# CameraBoard.net
KiCad netlist of a schematic drawn in EAGLE
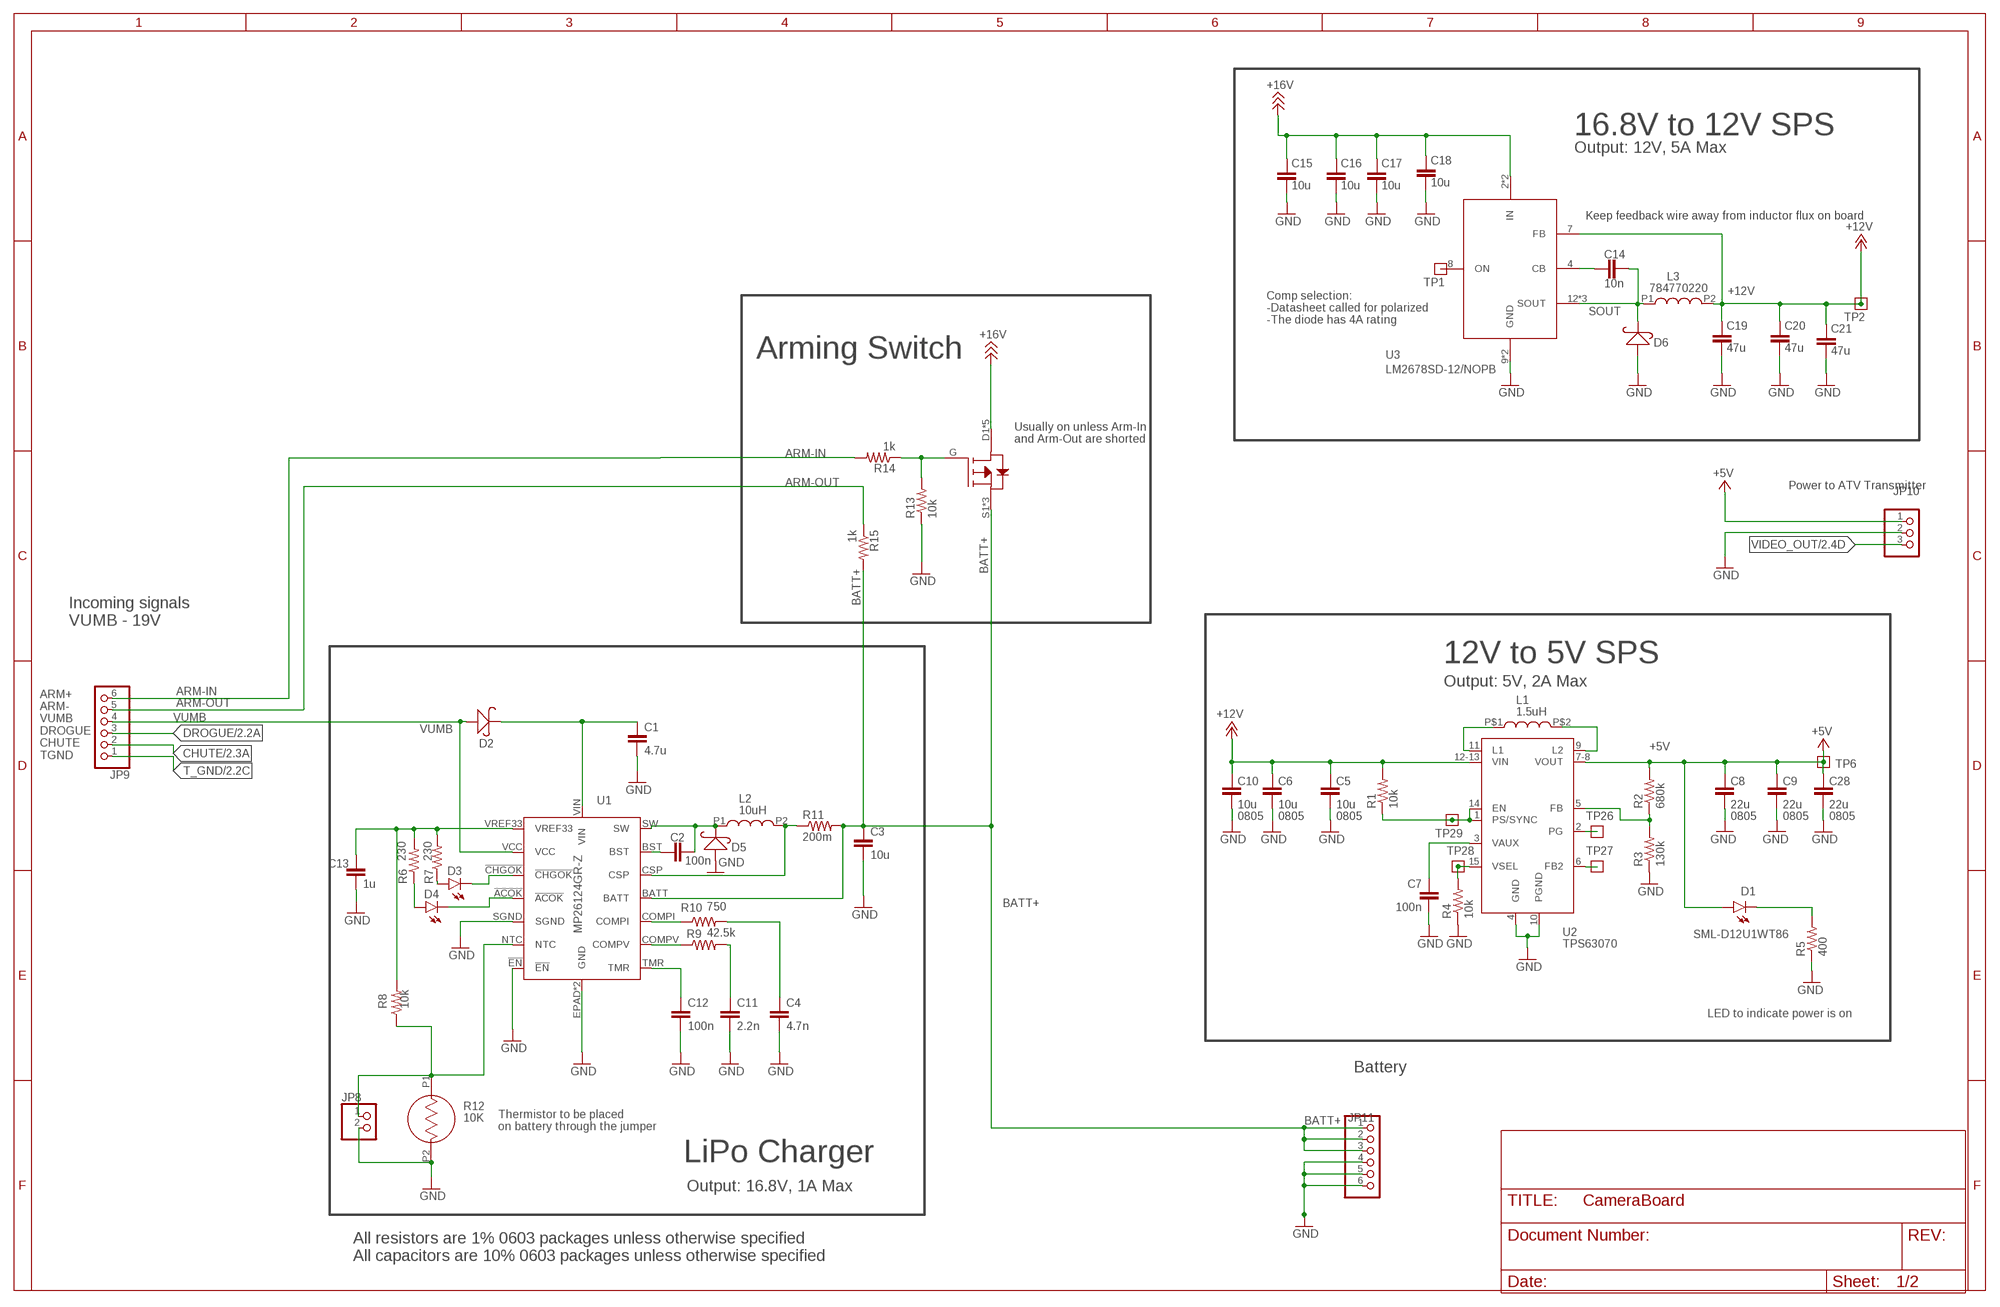
[diagram p0: schematic, sheet 1]
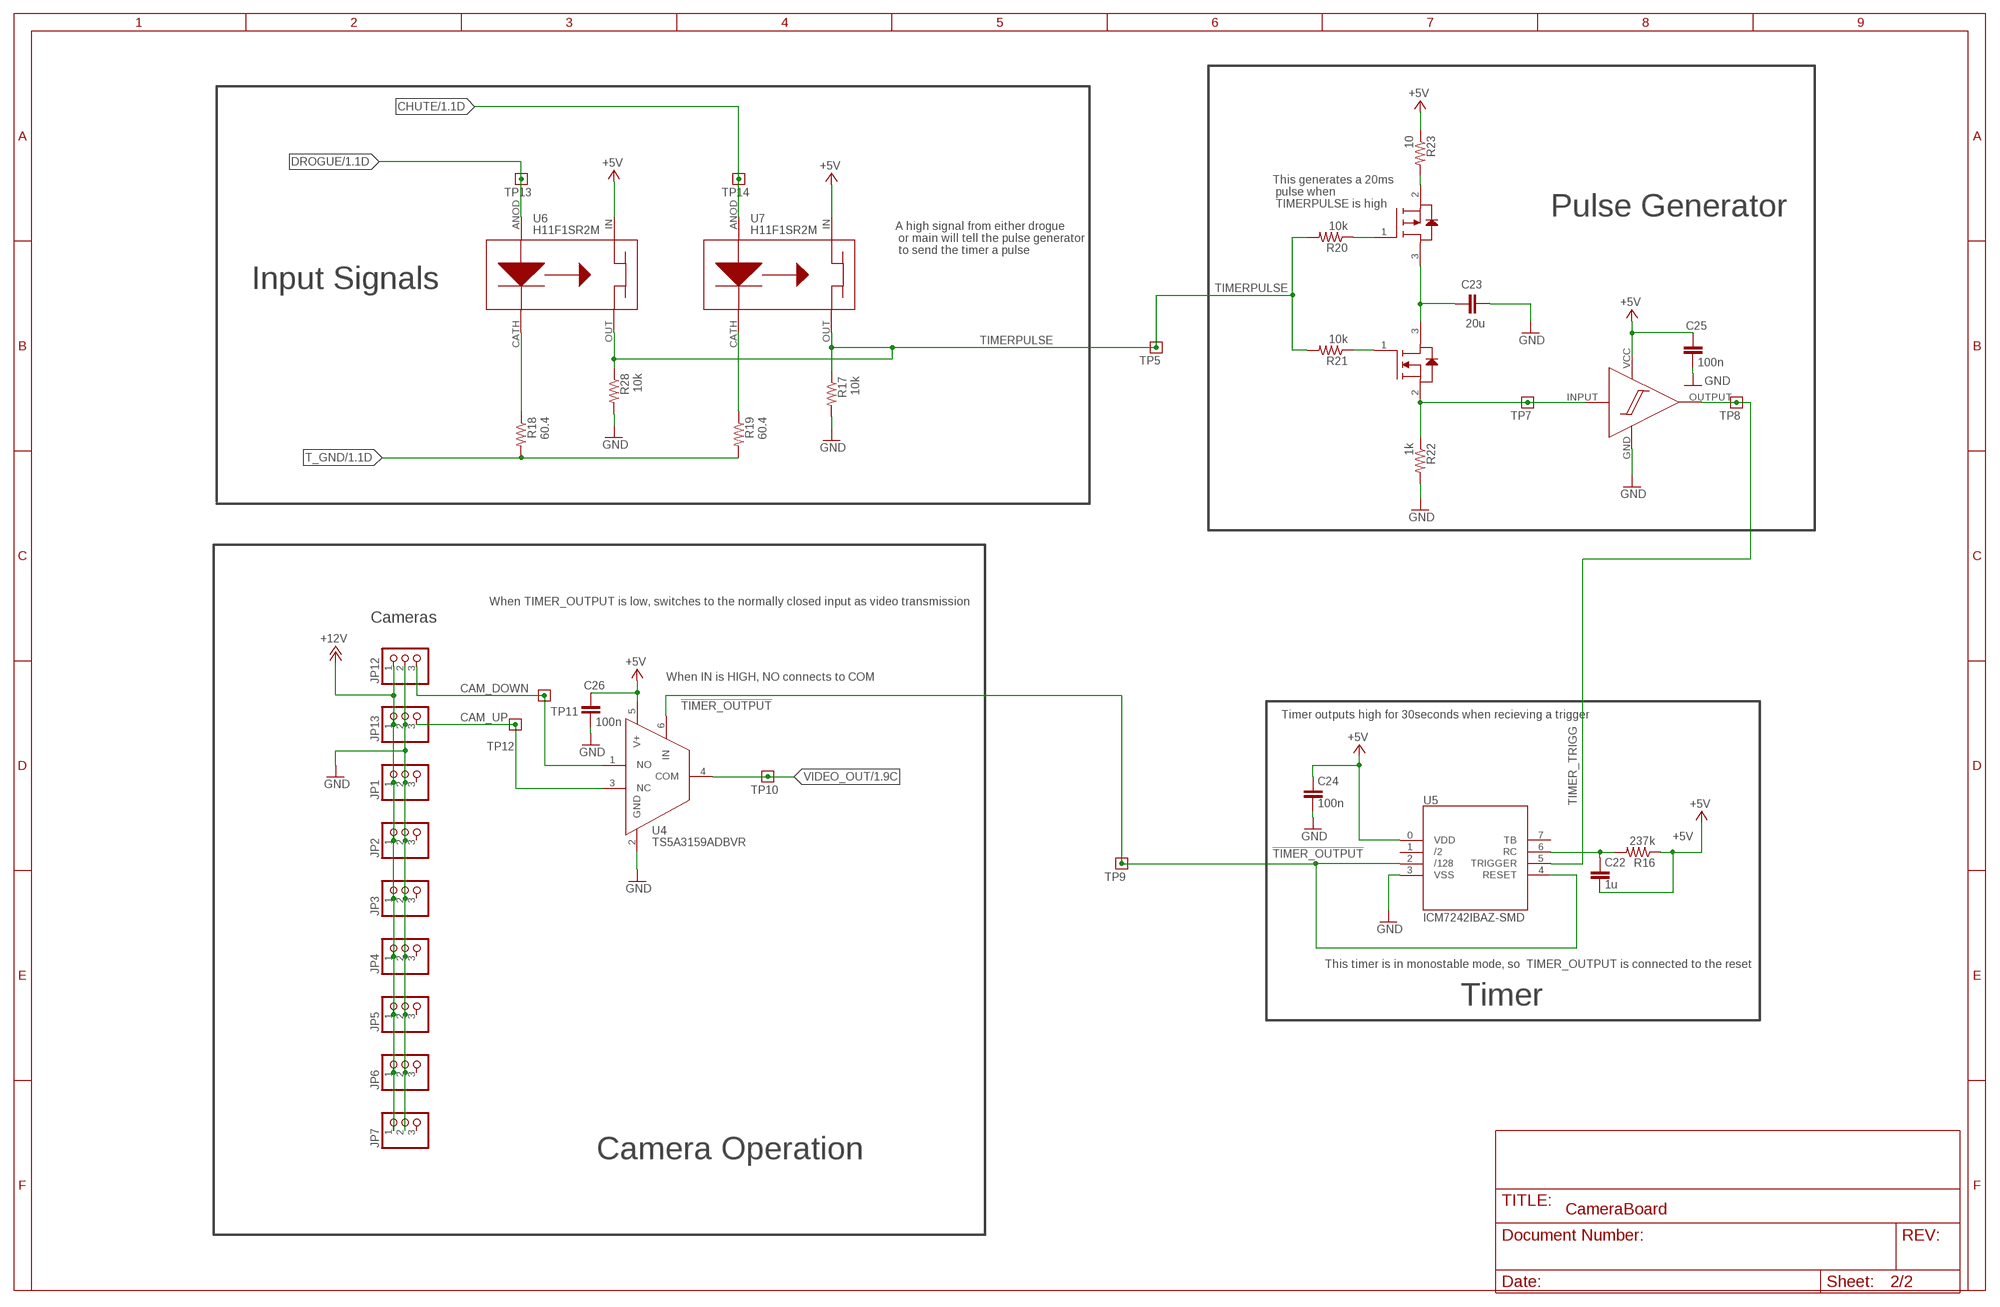
[diagram p1: schematic, sheet 2]

(export (version "E")
  (design (tool "Eeschema 10.0.6"))
  (components
    (comp (ref "C1")
      (value "4.7u")
      (footprint "eagle-import:.0603-A-NOSILK")
      (libsource (lib "eagle-import") (part "C-EU0603-A-NOSILK"))
    )
    (comp (ref "C2")
      (value "100n")
      (footprint "eagle-import:.0603-A-NOSILK")
      (libsource (lib "eagle-import") (part "C-EU0603-A-NOSILK"))
    )
    (comp (ref "C3")
      (value "10u")
      (footprint "eagle-import:.0603-A-NOSILK")
      (libsource (lib "eagle-import") (part "C-EU0603-A-NOSILK"))
    )
    (comp (ref "C4")
      (value "4.7n")
      (footprint "eagle-import:.0603-A-NOSILK")
      (libsource (lib "eagle-import") (part "C-EU0603-A-NOSILK"))
    )
    (comp (ref "C5")
      (value "10u")
      (footprint "eagle-import:.0805-C-NOSILK")
      (fields (field (name "MFR") "Samsung") (field (name "MPN") "CL05B104KO5NNNC"))
      (libsource (lib "eagle-import") (part "C-EU0805-C-NOSILK"))
    )
    (comp (ref "C6")
      (value "10u")
      (footprint "eagle-import:.0805-C-NOSILK")
      (libsource (lib "eagle-import") (part "C-EU0805-C-NOSILK"))
    )
    (comp (ref "C7")
      (value "100n")
      (footprint "eagle-import:.0603-C-NOSILK")
      (fields (field (name "MFR") "Samsung") (field (name "MPN") "CL05B104KO5NNNC"))
      (libsource (lib "eagle-import") (part "C-EU0603-C-NOSILK"))
    )
    (comp (ref "C8")
      (value "22u")
      (footprint "eagle-import:.0805-C-NOSILK")
      (fields (field (name "MFR") "Samsung") (field (name "MPN") "CL05B104KO5NNNC"))
      (libsource (lib "eagle-import") (part "C-EU0805-C-NOSILK"))
    )
    (comp (ref "C9")
      (value "22u")
      (footprint "eagle-import:.0805-C-NOSILK")
      (libsource (lib "eagle-import") (part "C-EU0805-C-NOSILK"))
    )
    (comp (ref "C10")
      (value "10u")
      (footprint "eagle-import:.0805-C-NOSILK")
      (libsource (lib "eagle-import") (part "C-EU0805-C-NOSILK"))
    )
    (comp (ref "C11")
      (value "2.2n")
      (footprint "eagle-import:.0603-A-NOSILK")
      (libsource (lib "eagle-import") (part "C-EU0603-A-NOSILK"))
    )
    (comp (ref "C12")
      (value "100n")
      (footprint "eagle-import:.0603-A-NOSILK")
      (libsource (lib "eagle-import") (part "C-EU0603-A-NOSILK"))
    )
    (comp (ref "C13")
      (value "1u")
      (footprint "eagle-import:.0603-A-NOSILK")
      (libsource (lib "eagle-import") (part "C-EU0603-A-NOSILK"))
    )
    (comp (ref "C14")
      (value "10n")
      (footprint "eagle-import:.0603-A-NOSILK")
      (libsource (lib "eagle-import") (part "C-EU0603-A-NOSILK"))
    )
    (comp (ref "C15")
      (value "10u")
      (footprint "eagle-import:.0805-B-NOSILK")
      (libsource (lib "eagle-import") (part "C-EU0805-B-NOSILK"))
    )
    (comp (ref "C16")
      (value "10u")
      (footprint "eagle-import:.0805-B-NOSILK")
      (libsource (lib "eagle-import") (part "C-EU0805-B-NOSILK"))
    )
    (comp (ref "C17")
      (value "10u")
      (footprint "eagle-import:.0805-B-NOSILK")
      (libsource (lib "eagle-import") (part "C-EU0805-B-NOSILK"))
    )
    (comp (ref "C18")
      (value "10u")
      (footprint "eagle-import:.0805-B-NOSILK")
      (libsource (lib "eagle-import") (part "C-EU0805-B-NOSILK"))
    )
    (comp (ref "C19")
      (value "47u")
      (footprint "eagle-import:1206-A")
      (libsource (lib "eagle-import") (part "C-EU1206-A"))
    )
    (comp (ref "C20")
      (value "47u")
      (footprint "eagle-import:1206-A")
      (libsource (lib "eagle-import") (part "C-EU1206-A"))
    )
    (comp (ref "C21")
      (value "47u")
      (footprint "eagle-import:1206-A")
      (libsource (lib "eagle-import") (part "C-EU1206-A"))
    )
    (comp (ref "C28")
      (value "22u")
      (footprint "eagle-import:.0805-C-NOSILK")
      (libsource (lib "eagle-import") (part "C-EU0805-C-NOSILK"))
    )
    (comp (ref "D1")
      (value "SML-D12U1WT86")
      (footprint "eagle-import:CHIPLED_0603")
      (fields (field (name "MPN") "SML-D12M1WT86"))
      (libsource (lib "eagle-import") (part "LEDCHIPLED_0603"))
    )
    (comp (ref "D2")
      (value "S2MA-13-F")
      (footprint "eagle-import:S2MA-13-F")
      (libsource (lib "eagle-import") (part "S2MA-13-F"))
    )
    (comp (ref "D3")
      (value "SML-D12U1WT86")
      (footprint "eagle-import:CHIPLED_0603")
      (fields (field (name "MPN") "SML-D12M1WT86"))
      (libsource (lib "eagle-import") (part "LEDCHIPLED_0603"))
    )
    (comp (ref "D4")
      (value "SML-D12U1WT86")
      (footprint "eagle-import:CHIPLED_0603")
      (fields (field (name "MPN") "SML-D12M1WT86"))
      (libsource (lib "eagle-import") (part "LEDCHIPLED_0603"))
    )
    (comp (ref "D5")
      (value "S2MA-13-F")
      (footprint "eagle-import:S2MA-13-F")
      (libsource (lib "eagle-import") (part "S2MA-13-F"))
    )
    (comp (ref "D6")
      (value "D_MBRS340T3G")
      (footprint "eagle-import:SMC")
      (fields (field (name "MANUFACTURER_PART_NUMBER") "MBRS340T3G"))
      (libsource (lib "eagle-import") (part "D_MBRS340T3G"))
    )
    (comp (ref "JP8")
      (value "PINHD-1X2")
      (footprint "eagle-import:1X02")
      (libsource (lib "eagle-import") (part "PINHD-1X2"))
    )
    (comp (ref "JP9")
      (value "PINHD-1X6")
      (footprint "eagle-import:1X06")
      (libsource (lib "eagle-import") (part "PINHD-1X6"))
    )
    (comp (ref "JP10")
      (value "PINHD-1X3")
      (footprint "eagle-import:1X03")
      (libsource (lib "eagle-import") (part "PINHD-1X3"))
    )
    (comp (ref "JP11")
      (value "PINHD-1X6")
      (footprint "eagle-import:1X06")
      (libsource (lib "eagle-import") (part "PINHD-1X6"))
    )
    (comp (ref "L1")
      (value "1.5uH")
      (footprint "eagle-import:IHLP2020CZER1R5M11")
      (fields (field (name "MFR") "Vishay Dale") (field (name "MPN") "IHLP2020BZER4R7M11"))
      (libsource (lib "eagle-import") (part "IHLP2020CZER1R5M11"))
    )
    (comp (ref "L2")
      (value "10uH")
      (footprint "eagle-import:1239AS-H-100M=P2")
      (fields (field (name "MPN") "1239AS-H-100M=P2"))
      (libsource (lib "eagle-import") (part "1239AS-H-100M=P2"))
    )
    (comp (ref "L3")
      (value "784770220")
      (footprint "eagle-import:784770220")
      (libsource (lib "eagle-import") (part "784770220"))
    )
    (comp (ref "Q1")
      (value "SI7465DP-T1-E3")
      (footprint "eagle-import:SI7465DP-T1-E3CT-ND")
      (fields (field (name "MFR") "Vishay Siliconix"))
      (libsource (lib "eagle-import") (part "SI7465DP-T1-E3"))
    )
    (comp (ref "R1")
      (value "10k")
      (footprint "eagle-import:.0603-C-NOSILK")
      (fields (field (name "MFR") "Samsung") (field (name "MPN") "RC1005F6653CS"))
      (libsource (lib "eagle-import") (part "R-US_0603-C-NOSILK"))
    )
    (comp (ref "R2")
      (value "680k")
      (footprint "eagle-import:.0603-C-NOSILK")
      (fields (field (name "MFR") "Samsung") (field (name "MPN") "RC1005F6653CS"))
      (libsource (lib "eagle-import") (part "R-US_0603-C-NOSILK"))
    )
    (comp (ref "R3")
      (value "130k")
      (footprint "eagle-import:.0603-C-NOSILK")
      (fields (field (name "MFR") "Samsung") (field (name "MPN") "RC1005F6653CS"))
      (libsource (lib "eagle-import") (part "R-US_0603-C-NOSILK"))
    )
    (comp (ref "R4")
      (value "10k")
      (footprint "eagle-import:.0603-C-NOSILK")
      (fields (field (name "MFR") "Samsung") (field (name "MPN") "RC1005F6653CS"))
      (libsource (lib "eagle-import") (part "R-US_0603-C-NOSILK"))
    )
    (comp (ref "R5")
      (value "400")
      (footprint "eagle-import:.0603-C-NOSILK")
      (fields (field (name "MFR") "Samsung") (field (name "MPN") "RC1005F6653CS"))
      (libsource (lib "eagle-import") (part "R-US_0603-C-NOSILK"))
    )
    (comp (ref "R6")
      (value "230")
      (footprint "eagle-import:.0603-A-NOSILK")
      (libsource (lib "eagle-import") (part "R-US_0603-A-NOSILK"))
    )
    (comp (ref "R7")
      (value "230")
      (footprint "eagle-import:.0603-A-NOSILK")
      (libsource (lib "eagle-import") (part "R-US_0603-A-NOSILK"))
    )
    (comp (ref "R8")
      (value "10k")
      (footprint "eagle-import:.0603-A-NOSILK")
      (libsource (lib "eagle-import") (part "R-US_0603-A-NOSILK"))
    )
    (comp (ref "R9")
      (value "42.5k")
      (footprint "eagle-import:.0603-A-NOSILK")
      (libsource (lib "eagle-import") (part "R-US_0603-A-NOSILK"))
    )
    (comp (ref "R10")
      (value "750")
      (footprint "eagle-import:.0603-A-NOSILK")
      (libsource (lib "eagle-import") (part "R-US_0603-A-NOSILK"))
    )
    (comp (ref "R11")
      (value "200m")
      (footprint "eagle-import:1206-A")
      (libsource (lib "eagle-import") (part "R-US_1206-A"))
    )
    (comp (ref "R12")
      (value "10K")
      (footprint "eagle-import:NHQ103B375T10")
      (fields (field (name "MPN") "NHQ103B375T10"))
      (libsource (lib "eagle-import") (part "NHQ103B375T10"))
    )
    (comp (ref "R13")
      (value "10k")
      (footprint "eagle-import:.0603-A-NOSILK")
      (libsource (lib "eagle-import") (part "R-US_0603-A-NOSILK"))
    )
    (comp (ref "R14")
      (value "1k")
      (footprint "eagle-import:.0603-A-NOSILK")
      (libsource (lib "eagle-import") (part "R-US_0603-A-NOSILK"))
    )
    (comp (ref "R15")
      (value "1k")
      (footprint "eagle-import:.0603-A-NOSILK")
      (libsource (lib "eagle-import") (part "R-US_0603-A-NOSILK"))
    )
    (comp (ref "TP1")
      (value "TEST-POINT")
      (footprint "eagle-import:2MM-TEST-POINT")
      (libsource (lib "eagle-import") (part "TEST-POINT"))
    )
    (comp (ref "TP2")
      (value "TEST-POINT")
      (footprint "eagle-import:2MM-TEST-POINT")
      (libsource (lib "eagle-import") (part "TEST-POINT"))
    )
    (comp (ref "TP6")
      (value "TEST-POINT")
      (footprint "eagle-import:2MM-TEST-POINT")
      (libsource (lib "eagle-import") (part "TEST-POINT"))
    )
    (comp (ref "TP26")
      (value "TEST-POINT")
      (footprint "eagle-import:2MM-TEST-POINT")
      (libsource (lib "eagle-import") (part "TEST-POINT"))
    )
    (comp (ref "TP27")
      (value "TEST-POINT")
      (footprint "eagle-import:2MM-TEST-POINT")
      (libsource (lib "eagle-import") (part "TEST-POINT"))
    )
    (comp (ref "TP28")
      (value "TEST-POINT")
      (footprint "eagle-import:2MM-TEST-POINT")
      (libsource (lib "eagle-import") (part "TEST-POINT"))
    )
    (comp (ref "TP29")
      (value "TEST-POINT")
      (footprint "eagle-import:2MM-TEST-POINT")
      (libsource (lib "eagle-import") (part "TEST-POINT"))
    )
    (comp (ref "U1")
      (value "MP26124GR-Z")
      (footprint "eagle-import:MP26124GR-Z")
      (libsource (lib "eagle-import") (part "MP26124GR-Z"))
    )
    (comp (ref "U2")
      (value "TPS63070")
      (footprint "eagle-import:TPS63070X")
      (fields (field (name "MPN") "TPS63070RNMR"))
      (libsource (lib "eagle-import") (part "TPS63070X"))
    )
    (comp (ref "U3")
      (value "LM2678SD-12/NOPB")
      (footprint "eagle-import:LM2678SD-12_NOPB")
      (libsource (lib "eagle-import") (part "LM2678SD-12/NOPB"))
    )
    (comp (ref "C22")
      (value "1u")
      (footprint "eagle-import:.0603-C-NOSILK")
      (libsource (lib "eagle-import") (part "C-EU0603-C-NOSILK"))
    )
    (comp (ref "C23")
      (value "20u")
      (footprint "eagle-import:.0603-C-NOSILK")
      (libsource (lib "eagle-import") (part "C-EU0603-C-NOSILK"))
    )
    (comp (ref "C24")
      (value "100n")
      (footprint "eagle-import:.0603-C-NOSILK")
      (libsource (lib "eagle-import") (part "C-EU0603-C-NOSILK"))
    )
    (comp (ref "C25")
      (value "100n")
      (footprint "eagle-import:.0603-C-NOSILK")
      (libsource (lib "eagle-import") (part "C-EU0603-C-NOSILK"))
    )
    (comp (ref "C26")
      (value "100n")
      (footprint "eagle-import:.0603-C-NOSILK")
      (libsource (lib "eagle-import") (part "C-EU0603-C-NOSILK"))
    )
    (comp (ref "JP1")
      (value "PINHD-1X3")
      (footprint "eagle-import:1X03")
      (libsource (lib "eagle-import") (part "PINHD-1X3"))
    )
    (comp (ref "JP2")
      (value "PINHD-1X3")
      (footprint "eagle-import:1X03")
      (libsource (lib "eagle-import") (part "PINHD-1X3"))
    )
    (comp (ref "JP3")
      (value "PINHD-1X3")
      (footprint "eagle-import:1X03")
      (libsource (lib "eagle-import") (part "PINHD-1X3"))
    )
    (comp (ref "JP4")
      (value "PINHD-1X3")
      (footprint "eagle-import:1X03")
      (libsource (lib "eagle-import") (part "PINHD-1X3"))
    )
    (comp (ref "JP5")
      (value "PINHD-1X3")
      (footprint "eagle-import:1X03")
      (libsource (lib "eagle-import") (part "PINHD-1X3"))
    )
    (comp (ref "JP6")
      (value "PINHD-1X3")
      (footprint "eagle-import:1X03")
      (libsource (lib "eagle-import") (part "PINHD-1X3"))
    )
    (comp (ref "JP7")
      (value "PINHD-1X3")
      (footprint "eagle-import:1X03")
      (libsource (lib "eagle-import") (part "PINHD-1X3"))
    )
    (comp (ref "JP12")
      (value "PINHD-1X3")
      (footprint "eagle-import:1X03")
      (libsource (lib "eagle-import") (part "PINHD-1X3"))
    )
    (comp (ref "JP13")
      (value "PINHD-1X3")
      (footprint "eagle-import:1X03")
      (libsource (lib "eagle-import") (part "PINHD-1X3"))
    )
    (comp (ref "Q2")
      (value "BVSS123LT1G")
      (footprint "eagle-import:BVSS123LT1G")
      (libsource (lib "eagle-import") (part "BVSS123LT1G"))
    )
    (comp (ref "Q3")
      (value "BSS84")
      (footprint "eagle-import:BSS84")
      (libsource (lib "eagle-import") (part "BSS84"))
    )
    (comp (ref "R16")
      (value "237k")
      (footprint "eagle-import:.0603-A-NOSILK")
      (libsource (lib "eagle-import") (part "R-US_0603-A-NOSILK"))
    )
    (comp (ref "R17")
      (value "10k")
      (footprint "eagle-import:.0603-C-NOSILK")
      (libsource (lib "eagle-import") (part "R-US_0603-C-NOSILK"))
    )
    (comp (ref "R18")
      (value "60.4")
      (footprint "eagle-import:.0603-C-NOSILK")
      (libsource (lib "eagle-import") (part "R-US_0603-C-NOSILK"))
    )
    (comp (ref "R19")
      (value "60.4")
      (footprint "eagle-import:.0603-C-NOSILK")
      (libsource (lib "eagle-import") (part "R-US_0603-C-NOSILK"))
    )
    (comp (ref "R20")
      (value "10k")
      (footprint "eagle-import:.0603-A-NOSILK")
      (libsource (lib "eagle-import") (part "R-US_0603-A-NOSILK"))
    )
    (comp (ref "R21")
      (value "10k")
      (footprint "eagle-import:.0603-A-NOSILK")
      (libsource (lib "eagle-import") (part "R-US_0603-A-NOSILK"))
    )
    (comp (ref "R22")
      (value "1k")
      (footprint "eagle-import:.0603-A-NOSILK")
      (libsource (lib "eagle-import") (part "R-US_0603-A-NOSILK"))
    )
    (comp (ref "R23")
      (value "10")
      (footprint "eagle-import:.0805-A-NOSILK")
      (libsource (lib "eagle-import") (part "R-US_0805-A-NOSILK"))
    )
    (comp (ref "R28")
      (value "10k")
      (footprint "eagle-import:.0603-C-NOSILK")
      (libsource (lib "eagle-import") (part "R-US_0603-C-NOSILK"))
    )
    (comp (ref "TP5")
      (value "TEST-POINT")
      (footprint "eagle-import:2MM-TEST-POINT")
      (libsource (lib "eagle-import") (part "TEST-POINT"))
    )
    (comp (ref "TP7")
      (value "TEST-POINT")
      (footprint "eagle-import:2MM-TEST-POINT")
      (libsource (lib "eagle-import") (part "TEST-POINT"))
    )
    (comp (ref "TP8")
      (value "TEST-POINT")
      (footprint "eagle-import:2MM-TEST-POINT")
      (libsource (lib "eagle-import") (part "TEST-POINT"))
    )
    (comp (ref "TP9")
      (value "TEST-POINT")
      (footprint "eagle-import:2MM-TEST-POINT")
      (libsource (lib "eagle-import") (part "TEST-POINT"))
    )
    (comp (ref "TP10")
      (value "TEST-POINT")
      (footprint "eagle-import:2MM-TEST-POINT")
      (libsource (lib "eagle-import") (part "TEST-POINT"))
    )
    (comp (ref "TP11")
      (value "TEST-POINT")
      (footprint "eagle-import:2MM-TEST-POINT")
      (libsource (lib "eagle-import") (part "TEST-POINT"))
    )
    (comp (ref "TP12")
      (value "TEST-POINT")
      (footprint "eagle-import:2MM-TEST-POINT")
      (libsource (lib "eagle-import") (part "TEST-POINT"))
    )
    (comp (ref "TP13")
      (value "TEST-POINT")
      (footprint "eagle-import:2MM-TEST-POINT")
      (libsource (lib "eagle-import") (part "TEST-POINT"))
    )
    (comp (ref "TP14")
      (value "TEST-POINT")
      (footprint "eagle-import:2MM-TEST-POINT")
      (libsource (lib "eagle-import") (part "TEST-POINT"))
    )
    (comp (ref "U4")
      (value "TS5A3159ADBVR")
      (footprint "eagle-import:TS5A3159ADBVR")
      (libsource (lib "eagle-import") (part "TS5A3159ADBVR"))
    )
    (comp (ref "U5")
      (value "ICM7242IBAZ-SMD")
      (footprint "eagle-import:ICM7242IBAZ-SMD")
      (fields (field (name "MPN") "ICM7242IBAZ"))
      (libsource (lib "eagle-import") (part "ICM7242IBAZ-SMD"))
    )
    (comp (ref "U6")
      (value "H11F1SR2M")
      (footprint "eagle-import:H11F1SR2M")
      (libsource (lib "eagle-import") (part "H11F1SR2M"))
    )
    (comp (ref "U7")
      (value "H11F1SR2M")
      (footprint "eagle-import:H11F1SR2M")
      (libsource (lib "eagle-import") (part "H11F1SR2M"))
    )
    (comp (ref "U8")
      (value "SN74LVC1G17DCKR")
      (footprint "eagle-import:SN74LVC1G17DCKR")
      (libsource (lib "eagle-import") (part "SN74LVC1G17DCKR"))
    )
  )
  (nets
    (net (code "1") (name "+5V") (class "Default")
      (node (ref "C22") (pin "2") (pinfunction "2_2") (pintype "passive"))
      (node (ref "C24") (pin "1") (pinfunction "1_1") (pintype "passive"))
      (node (ref "C25") (pin "2") (pinfunction "2_2") (pintype "passive"))
      (node (ref "C26") (pin "2") (pinfunction "2_2") (pintype "passive"))
      (node (ref "C28") (pin "1") (pinfunction "1_1") (pintype "passive"))
      (node (ref "C8") (pin "1") (pinfunction "1_1") (pintype "passive"))
      (node (ref "C9") (pin "1") (pinfunction "1_1") (pintype "passive"))
      (node (ref "D1") (pin "A") (pinfunction "A_A") (pintype "passive"))
      (node (ref "JP10") (pin "1") (pinfunction "1_1") (pintype "passive"))
      (node (ref "R16") (pin "1") (pinfunction "1_1") (pintype "passive"))
      (node (ref "R2") (pin "2") (pinfunction "2_2") (pintype "passive"))
      (node (ref "R23") (pin "1") (pinfunction "1_1") (pintype "passive"))
      (node (ref "TP6") (pin "1") (pinfunction "1_1") (pintype "passive"))
      (node (ref "U2") (pin "7-8") (pinfunction "VOUT_7-8") (pintype "power_in"))
      (node (ref "U4") (pin "5") (pinfunction "V+_5") (pintype "bidirectional"))
      (node (ref "U5") (pin "0") (pinfunction "VDD_0") (pintype "bidirectional"))
      (node (ref "U6") (pin "IN") (pinfunction "IN_IN") (pintype "bidirectional"))
      (node (ref "U7") (pin "IN") (pinfunction "IN_IN") (pintype "bidirectional"))
      (node (ref "U8") (pin "VCC") (pinfunction "VCC_VCC") (pintype "bidirectional"))
    )
    (net (code "2") (name "+12V") (class "Default")
      (node (ref "C10") (pin "1") (pinfunction "1_1") (pintype "passive"))
      (node (ref "C19") (pin "1") (pinfunction "1_1") (pintype "passive"))
      (node (ref "C20") (pin "1") (pinfunction "1_1") (pintype "passive"))
      (node (ref "C21") (pin "1") (pinfunction "1_1") (pintype "passive"))
      (node (ref "C5") (pin "1") (pinfunction "1_1") (pintype "passive"))
      (node (ref "C6") (pin "1") (pinfunction "1_1") (pintype "passive"))
      (node (ref "JP1") (pin "1") (pinfunction "1_1") (pintype "passive"))
      (node (ref "JP12") (pin "1") (pinfunction "1_1") (pintype "passive"))
      (node (ref "JP13") (pin "1") (pinfunction "1_1") (pintype "passive"))
      (node (ref "JP2") (pin "1") (pinfunction "1_1") (pintype "passive"))
      (node (ref "JP3") (pin "1") (pinfunction "1_1") (pintype "passive"))
      (node (ref "JP4") (pin "1") (pinfunction "1_1") (pintype "passive"))
      (node (ref "JP5") (pin "1") (pinfunction "1_1") (pintype "passive"))
      (node (ref "JP6") (pin "1") (pinfunction "1_1") (pintype "passive"))
      (node (ref "JP7") (pin "1") (pinfunction "1_1") (pintype "passive"))
      (node (ref "L3") (pin "P2") (pinfunction "P$2_P2") (pintype "bidirectional"))
      (node (ref "R1") (pin "2") (pinfunction "2_2") (pintype "passive"))
      (node (ref "TP2") (pin "1") (pinfunction "1_1") (pintype "passive"))
      (node (ref "U2") (pin "12-13") (pinfunction "VIN_12-13") (pintype "power_in"))
      (node (ref "U3") (pin "7") (pinfunction "FB_7") (pintype "bidirectional"))
    )
    (net (code "3") (name "+16V") (class "Default")
      (node (ref "C15") (pin "1") (pinfunction "1_1") (pintype "passive"))
      (node (ref "C16") (pin "1") (pinfunction "1_1") (pintype "passive"))
      (node (ref "C17") (pin "1") (pinfunction "1_1") (pintype "passive"))
      (node (ref "C18") (pin "1") (pinfunction "1_1") (pintype "passive"))
      (node (ref "Q1") (pin "D1") (pinfunction "D_D1") (pintype "bidirectional"))
      (node (ref "Q1") (pin "D2") (pinfunction "D_D2") (pintype "bidirectional"))
      (node (ref "Q1") (pin "D3") (pinfunction "D_D3") (pintype "bidirectional"))
      (node (ref "Q1") (pin "D4") (pinfunction "D_D4") (pintype "bidirectional"))
      (node (ref "Q1") (pin "DPAD") (pinfunction "D_DPAD") (pintype "bidirectional"))
      (node (ref "U3") (pin "2") (pinfunction "IN_2") (pintype "bidirectional"))
      (node (ref "U3") (pin "3") (pinfunction "IN_3") (pintype "bidirectional"))
    )
    (net (code "4") (name "ARM-IN") (class "Default")
      (node (ref "JP9") (pin "6") (pinfunction "6_6") (pintype "passive"))
      (node (ref "R14") (pin "2") (pinfunction "2_2") (pintype "passive"))
    )
    (net (code "5") (name "ARM-OUT") (class "Default")
      (node (ref "JP9") (pin "5") (pinfunction "5_5") (pintype "passive"))
      (node (ref "R15") (pin "1") (pinfunction "1_1") (pintype "passive"))
    )
    (net (code "6") (name "BATT+") (class "Default")
      (node (ref "C3") (pin "1") (pinfunction "1_1") (pintype "passive"))
      (node (ref "JP11") (pin "1") (pinfunction "1_1") (pintype "passive"))
      (node (ref "JP11") (pin "2") (pinfunction "2_2") (pintype "passive"))
      (node (ref "JP11") (pin "3") (pinfunction "3_3") (pintype "passive"))
      (node (ref "Q1") (pin "S1") (pinfunction "S_S1") (pintype "bidirectional"))
      (node (ref "Q1") (pin "S2") (pinfunction "S_S2") (pintype "bidirectional"))
      (node (ref "Q1") (pin "S3") (pinfunction "S_S3") (pintype "bidirectional"))
      (node (ref "R11") (pin "2") (pinfunction "2_2") (pintype "passive"))
      (node (ref "R15") (pin "2") (pinfunction "2_2") (pintype "passive"))
      (node (ref "U1") (pin "BATT") (pinfunction "BATT_BATT") (pintype "bidirectional"))
    )
    (net (code "7") (name "CAM_DOWN") (class "Default")
      (node (ref "JP12") (pin "3") (pinfunction "3_3") (pintype "passive"))
      (node (ref "TP11") (pin "1") (pinfunction "1_1") (pintype "passive"))
      (node (ref "U4") (pin "1") (pinfunction "NO_1") (pintype "bidirectional"))
    )
    (net (code "8") (name "CAM_UP") (class "Default")
      (node (ref "JP13") (pin "3") (pinfunction "3_3") (pintype "passive"))
      (node (ref "TP12") (pin "1") (pinfunction "1_1") (pintype "passive"))
      (node (ref "U4") (pin "3") (pinfunction "NC_3") (pintype "bidirectional"))
    )
    (net (code "9") (name "CHUTE") (class "Default")
      (node (ref "JP9") (pin "2") (pinfunction "2_2") (pintype "passive"))
      (node (ref "TP14") (pin "1") (pinfunction "1_1") (pintype "passive"))
      (node (ref "U7") (pin "ANOD") (pinfunction "ANOD_ANOD") (pintype "bidirectional"))
    )
    (net (code "10") (name "DROGUE") (class "Default")
      (node (ref "JP9") (pin "3") (pinfunction "3_3") (pintype "passive"))
      (node (ref "TP13") (pin "1") (pinfunction "1_1") (pintype "passive"))
      (node (ref "U6") (pin "ANOD") (pinfunction "ANOD_ANOD") (pintype "bidirectional"))
    )
    (net (code "11") (name "GND") (class "Default")
      (node (ref "C1") (pin "2") (pinfunction "2_2") (pintype "passive"))
      (node (ref "C10") (pin "2") (pinfunction "2_2") (pintype "passive"))
      (node (ref "C11") (pin "2") (pinfunction "2_2") (pintype "passive"))
      (node (ref "C12") (pin "2") (pinfunction "2_2") (pintype "passive"))
      (node (ref "C13") (pin "2") (pinfunction "2_2") (pintype "passive"))
      (node (ref "C15") (pin "2") (pinfunction "2_2") (pintype "passive"))
      (node (ref "C16") (pin "2") (pinfunction "2_2") (pintype "passive"))
      (node (ref "C17") (pin "2") (pinfunction "2_2") (pintype "passive"))
      (node (ref "C18") (pin "2") (pinfunction "2_2") (pintype "passive"))
      (node (ref "C19") (pin "2") (pinfunction "2_2") (pintype "passive"))
      (node (ref "C20") (pin "2") (pinfunction "2_2") (pintype "passive"))
      (node (ref "C21") (pin "2") (pinfunction "2_2") (pintype "passive"))
      (node (ref "C23") (pin "2") (pinfunction "2_2") (pintype "passive"))
      (node (ref "C24") (pin "2") (pinfunction "2_2") (pintype "passive"))
      (node (ref "C25") (pin "1") (pinfunction "1_1") (pintype "passive"))
      (node (ref "C26") (pin "1") (pinfunction "1_1") (pintype "passive"))
      (node (ref "C28") (pin "2") (pinfunction "2_2") (pintype "passive"))
      (node (ref "C3") (pin "2") (pinfunction "2_2") (pintype "passive"))
      (node (ref "C4") (pin "2") (pinfunction "2_2") (pintype "passive"))
      (node (ref "C5") (pin "2") (pinfunction "2_2") (pintype "passive"))
      (node (ref "C6") (pin "2") (pinfunction "2_2") (pintype "passive"))
      (node (ref "C7") (pin "2") (pinfunction "2_2") (pintype "passive"))
      (node (ref "C8") (pin "2") (pinfunction "2_2") (pintype "passive"))
      (node (ref "C9") (pin "2") (pinfunction "2_2") (pintype "passive"))
      (node (ref "D5") (pin "ANODE") (pinfunction "+_ANODE") (pintype "passive"))
      (node (ref "D6") (pin "2") (pinfunction "+_2") (pintype "passive"))
      (node (ref "JP1") (pin "2") (pinfunction "2_2") (pintype "passive"))
      (node (ref "JP10") (pin "2") (pinfunction "2_2") (pintype "passive"))
      (node (ref "JP11") (pin "4") (pinfunction "4_4") (pintype "passive"))
      (node (ref "JP11") (pin "5") (pinfunction "5_5") (pintype "passive"))
      (node (ref "JP11") (pin "6") (pinfunction "6_6") (pintype "passive"))
      (node (ref "JP12") (pin "2") (pinfunction "2_2") (pintype "passive"))
      (node (ref "JP13") (pin "2") (pinfunction "2_2") (pintype "passive"))
      (node (ref "JP2") (pin "2") (pinfunction "2_2") (pintype "passive"))
      (node (ref "JP3") (pin "2") (pinfunction "2_2") (pintype "passive"))
      (node (ref "JP4") (pin "2") (pinfunction "2_2") (pintype "passive"))
      (node (ref "JP5") (pin "2") (pinfunction "2_2") (pintype "passive"))
      (node (ref "JP6") (pin "2") (pinfunction "2_2") (pintype "passive"))
      (node (ref "JP7") (pin "2") (pinfunction "2_2") (pintype "passive"))
      (node (ref "JP8") (pin "2") (pinfunction "2_2") (pintype "passive"))
      (node (ref "R12") (pin "P2") (pinfunction "P$2_P2") (pintype "bidirectional"))
      (node (ref "R13") (pin "1") (pinfunction "1_1") (pintype "passive"))
      (node (ref "R17") (pin "2") (pinfunction "2_2") (pintype "passive"))
      (node (ref "R22") (pin "2") (pinfunction "2_2") (pintype "passive"))
      (node (ref "R28") (pin "2") (pinfunction "2_2") (pintype "passive"))
      (node (ref "R3") (pin "1") (pinfunction "1_1") (pintype "passive"))
      (node (ref "R4") (pin "1") (pinfunction "1_1") (pintype "passive"))
      (node (ref "R5") (pin "1") (pinfunction "1_1") (pintype "passive"))
      (node (ref "U1") (pin "!EN") (pinfunction "~{EN}_!EN") (pintype "bidirectional"))
      (node (ref "U1") (pin "EPAD") (pinfunction "GND_EPAD") (pintype "bidirectional"))
      (node (ref "U1") (pin "GND") (pinfunction "GND_GND") (pintype "bidirectional"))
      (node (ref "U1") (pin "SGND") (pinfunction "SGND_SGND") (pintype "bidirectional"))
      (node (ref "U2") (pin "10") (pinfunction "PGND_10") (pintype "power_in"))
      (node (ref "U2") (pin "4") (pinfunction "GND_4") (pintype "power_in"))
      (node (ref "U3") (pin "9") (pinfunction "GND_9") (pintype "bidirectional"))
      (node (ref "U3") (pin "DAP") (pinfunction "GND_DAP") (pintype "bidirectional"))
      (node (ref "U4") (pin "2") (pinfunction "GND_2") (pintype "bidirectional"))
      (node (ref "U5") (pin "3") (pinfunction "VSS_3") (pintype "bidirectional"))
      (node (ref "U8") (pin "GND") (pinfunction "GND_GND") (pintype "bidirectional"))
    )
    (net (code "12") (name "Net-(C2-Pad2)") (class "Default")
      (node (ref "C2") (pin "2") (pinfunction "2_2") (pintype "passive"))
      (node (ref "U1") (pin "BST") (pinfunction "BST_BST") (pintype "bidirectional"))
    )
    (net (code "13") (name "Net-(C4-Pad1)") (class "Default")
      (node (ref "C4") (pin "1") (pinfunction "1_1") (pintype "passive"))
      (node (ref "R10") (pin "2") (pinfunction "2_2") (pintype "passive"))
    )
    (net (code "14") (name "Net-(C11-Pad1)") (class "Default")
      (node (ref "C11") (pin "1") (pinfunction "1_1") (pintype "passive"))
      (node (ref "R9") (pin "2") (pinfunction "2_2") (pintype "passive"))
    )
    (net (code "15") (name "Net-(C12-Pad1)") (class "Default")
      (node (ref "C12") (pin "1") (pinfunction "1_1") (pintype "passive"))
      (node (ref "U1") (pin "TMR") (pinfunction "TMR_TMR") (pintype "bidirectional"))
    )
    (net (code "16") (name "Net-(C13-Pad1)") (class "Default")
      (node (ref "C13") (pin "1") (pinfunction "1_1") (pintype "passive"))
      (node (ref "R6") (pin "2") (pinfunction "2_2") (pintype "passive"))
      (node (ref "R7") (pin "2") (pinfunction "2_2") (pintype "passive"))
      (node (ref "R8") (pin "2") (pinfunction "2_2") (pintype "passive"))
      (node (ref "U1") (pin "VREF33") (pinfunction "VREF33_VREF33") (pintype "bidirectional"))
    )
    (net (code "17") (name "Net-(D1-PadC)") (class "Default")
      (node (ref "D1") (pin "C") (pinfunction "C_C") (pintype "passive"))
      (node (ref "R5") (pin "2") (pinfunction "2_2") (pintype "passive"))
    )
    (net (code "18") (name "Net-(D2--)") (class "Default")
      (node (ref "C1") (pin "1") (pinfunction "1_1") (pintype "passive"))
      (node (ref "D2") (pin "CATHODE") (pinfunction "-_CATHODE") (pintype "passive"))
      (node (ref "U1") (pin "VIN") (pinfunction "VIN_VIN") (pintype "bidirectional"))
    )
    (net (code "19") (name "Net-(D3-PadA)") (class "Default")
      (node (ref "D3") (pin "A") (pinfunction "A_A") (pintype "passive"))
      (node (ref "R7") (pin "1") (pinfunction "1_1") (pintype "passive"))
    )
    (net (code "20") (name "Net-(D4-PadA)") (class "Default")
      (node (ref "D4") (pin "A") (pinfunction "A_A") (pintype "passive"))
      (node (ref "R6") (pin "1") (pinfunction "1_1") (pintype "passive"))
    )
    (net (code "21") (name "Net-(D5--)") (class "Default")
      (node (ref "C2") (pin "1") (pinfunction "1_1") (pintype "passive"))
      (node (ref "D5") (pin "CATHODE") (pinfunction "-_CATHODE") (pintype "passive"))
      (node (ref "L2") (pin "P1") (pinfunction "P$1_P1") (pintype "bidirectional"))
      (node (ref "U1") (pin "SW") (pinfunction "SW_SW") (pintype "bidirectional"))
    )
    (net (code "22") (name "Net-(L2-P$2)") (class "Default")
      (node (ref "L2") (pin "P2") (pinfunction "P$2_P2") (pintype "bidirectional"))
      (node (ref "R11") (pin "1") (pinfunction "1_1") (pintype "passive"))
      (node (ref "U1") (pin "CSP") (pinfunction "CSP_CSP") (pintype "bidirectional"))
    )
    (net (code "23") (name "Net-(Q1-PadG)") (class "Default")
      (node (ref "Q1") (pin "G") (pinfunction "G_G") (pintype "bidirectional"))
      (node (ref "R13") (pin "2") (pinfunction "2_2") (pintype "passive"))
      (node (ref "R14") (pin "1") (pinfunction "1_1") (pintype "passive"))
    )
    (net (code "24") (name "Net-(Q2-D)") (class "Default")
      (node (ref "C23") (pin "1") (pinfunction "1_1") (pintype "passive"))
      (node (ref "Q2") (pin "3") (pinfunction "D_3") (pintype "bidirectional"))
      (node (ref "Q3") (pin "3") (pinfunction "D_3") (pintype "bidirectional"))
    )
    (net (code "25") (name "Net-(Q2-G)") (class "Default")
      (node (ref "Q2") (pin "1") (pinfunction "G_1") (pintype "bidirectional"))
      (node (ref "R21") (pin "1") (pinfunction "1_1") (pintype "passive"))
    )
    (net (code "26") (name "Net-(Q2-S)") (class "Default")
      (node (ref "Q2") (pin "2") (pinfunction "S_2") (pintype "bidirectional"))
      (node (ref "R22") (pin "1") (pinfunction "1_1") (pintype "passive"))
      (node (ref "TP7") (pin "1") (pinfunction "1_1") (pintype "passive"))
      (node (ref "U8") (pin "INPUT") (pinfunction "A_INPUT") (pintype "bidirectional"))
    )
    (net (code "27") (name "Net-(Q3-G)") (class "Default")
      (node (ref "Q3") (pin "1") (pinfunction "G_1") (pintype "bidirectional"))
      (node (ref "R20") (pin "1") (pinfunction "1_1") (pintype "passive"))
    )
    (net (code "28") (name "Net-(Q3-S)") (class "Default")
      (node (ref "Q3") (pin "2") (pinfunction "S_2") (pintype "bidirectional"))
      (node (ref "R23") (pin "2") (pinfunction "2_2") (pintype "passive"))
    )
    (net (code "29") (name "Net-(R9-Pad1)") (class "Default")
      (node (ref "R9") (pin "1") (pinfunction "1_1") (pintype "passive"))
      (node (ref "U1") (pin "COMPV") (pinfunction "COMPV_COMPV") (pintype "bidirectional"))
    )
    (net (code "30") (name "Net-(R10-Pad1)") (class "Default")
      (node (ref "R10") (pin "1") (pinfunction "1_1") (pintype "passive"))
      (node (ref "U1") (pin "COMPI") (pinfunction "COMPI_COMPI") (pintype "bidirectional"))
    )
    (net (code "31") (name "Net-(R12-P$1)") (class "Default")
      (node (ref "JP8") (pin "1") (pinfunction "1_1") (pintype "passive"))
      (node (ref "R12") (pin "P1") (pinfunction "P$1_P1") (pintype "bidirectional"))
      (node (ref "R8") (pin "1") (pinfunction "1_1") (pintype "passive"))
      (node (ref "U1") (pin "NTC") (pinfunction "NTC_NTC") (pintype "bidirectional"))
    )
    (net (code "32") (name "Net-(U1-~{ACOK})") (class "Default")
      (node (ref "D4") (pin "C") (pinfunction "C_C") (pintype "passive"))
      (node (ref "U1") (pin "!ACOK") (pinfunction "~{ACOK}_!ACOK") (pintype "bidirectional"))
    )
    (net (code "33") (name "Net-(U1-~{CHGOK})") (class "Default")
      (node (ref "D3") (pin "C") (pinfunction "C_C") (pintype "passive"))
      (node (ref "U1") (pin "!CHGOK") (pinfunction "~{CHGOK}_!CHGOK") (pintype "bidirectional"))
    )
    (net (code "34") (name "Net-(U2-EN)") (class "Default")
      (node (ref "R1") (pin "1") (pinfunction "1_1") (pintype "passive"))
      (node (ref "TP29") (pin "1") (pinfunction "1_1") (pintype "passive"))
      (node (ref "U2") (pin "1") (pinfunction "PS/SYNC_1") (pintype "input"))
      (node (ref "U2") (pin "14") (pinfunction "EN_14") (pintype "input"))
    )
    (net (code "35") (name "Net-(U2-FB)") (class "Default")
      (node (ref "R2") (pin "1") (pinfunction "1_1") (pintype "passive"))
      (node (ref "R3") (pin "2") (pinfunction "2_2") (pintype "passive"))
      (node (ref "U2") (pin "5") (pinfunction "FB_5") (pintype "passive"))
    )
    (net (code "36") (name "Net-(U2-FB2)") (class "Default")
      (node (ref "TP27") (pin "1") (pinfunction "1_1") (pintype "passive"))
      (node (ref "U2") (pin "6") (pinfunction "FB2_6") (pintype "passive"))
    )
    (net (code "37") (name "Net-(U2-L1)") (class "Default")
      (node (ref "L1") (pin "P$1") (pinfunction "P$1_P$1") (pintype "bidirectional"))
      (node (ref "U2") (pin "11") (pinfunction "L1_11") (pintype "passive"))
    )
    (net (code "38") (name "Net-(U2-L2)") (class "Default")
      (node (ref "L1") (pin "P$2") (pinfunction "P$2_P$2") (pintype "bidirectional"))
      (node (ref "U2") (pin "9") (pinfunction "L2_9") (pintype "passive"))
    )
    (net (code "39") (name "Net-(U2-PG)") (class "Default")
      (node (ref "TP26") (pin "1") (pinfunction "1_1") (pintype "passive"))
      (node (ref "U2") (pin "2") (pinfunction "PG_2") (pintype "open_collector"))
    )
    (net (code "40") (name "Net-(U2-VAUX)") (class "Default")
      (node (ref "C7") (pin "1") (pinfunction "1_1") (pintype "passive"))
      (node (ref "U2") (pin "3") (pinfunction "VAUX_3") (pintype "output"))
    )
    (net (code "41") (name "Net-(U2-VSEL)") (class "Default")
      (node (ref "R4") (pin "2") (pinfunction "2_2") (pintype "passive"))
      (node (ref "TP28") (pin "1") (pinfunction "1_1") (pintype "passive"))
      (node (ref "U2") (pin "15") (pinfunction "VSEL_15") (pintype "input"))
    )
    (net (code "42") (name "Net-(U3-CB)") (class "Default")
      (node (ref "C14") (pin "2") (pinfunction "2_2") (pintype "passive"))
      (node (ref "U3") (pin "4") (pinfunction "CB_4") (pintype "bidirectional"))
    )
    (net (code "43") (name "Net-(U3-ON)") (class "Default")
      (node (ref "TP1") (pin "1") (pinfunction "1_1") (pintype "passive"))
      (node (ref "U3") (pin "8") (pinfunction "ON_8") (pintype "bidirectional"))
    )
    (net (code "44") (name "Net-(U5-RC)") (class "Default")
      (node (ref "C22") (pin "1") (pinfunction "1_1") (pintype "passive"))
      (node (ref "R16") (pin "2") (pinfunction "2_2") (pintype "passive"))
      (node (ref "U5") (pin "6") (pinfunction "RC_6") (pintype "bidirectional"))
    )
    (net (code "45") (name "Net-(U6-CAT)") (class "Default")
      (node (ref "R18") (pin "1") (pinfunction "1_1") (pintype "passive"))
      (node (ref "U6") (pin "CATH") (pinfunction "CAT_CATH") (pintype "bidirectional"))
    )
    (net (code "46") (name "Net-(U7-CAT)") (class "Default")
      (node (ref "R19") (pin "1") (pinfunction "1_1") (pintype "passive"))
      (node (ref "U7") (pin "CATH") (pinfunction "CAT_CATH") (pintype "bidirectional"))
    )
    (net (code "47") (name "SOUT") (class "Default")
      (node (ref "C14") (pin "1") (pinfunction "1_1") (pintype "passive"))
      (node (ref "D6") (pin "1") (pinfunction "-_1") (pintype "passive"))
      (node (ref "L3") (pin "P1") (pinfunction "P$1_P1") (pintype "bidirectional"))
      (node (ref "U3") (pin "12") (pinfunction "SOUT_12") (pintype "bidirectional"))
      (node (ref "U3") (pin "13") (pinfunction "SOUT_13") (pintype "bidirectional"))
      (node (ref "U3") (pin "14") (pinfunction "SOUT_14") (pintype "bidirectional"))
    )
    (net (code "48") (name "TIMERPULSE") (class "Default")
      (node (ref "R17") (pin "1") (pinfunction "1_1") (pintype "passive"))
      (node (ref "R20") (pin "2") (pinfunction "2_2") (pintype "passive"))
      (node (ref "R21") (pin "2") (pinfunction "2_2") (pintype "passive"))
      (node (ref "R28") (pin "1") (pinfunction "1_1") (pintype "passive"))
      (node (ref "TP5") (pin "1") (pinfunction "1_1") (pintype "passive"))
      (node (ref "U6") (pin "OUT") (pinfunction "OUT_OUT") (pintype "bidirectional"))
      (node (ref "U7") (pin "OUT") (pinfunction "OUT_OUT") (pintype "bidirectional"))
    )
    (net (code "49") (name "TIMER_TRIGG") (class "Default")
      (node (ref "TP8") (pin "1") (pinfunction "1_1") (pintype "passive"))
      (node (ref "U5") (pin "5") (pinfunction "TRIGGER_5") (pintype "bidirectional"))
      (node (ref "U8") (pin "OUTPUT") (pinfunction "Y_OUTPUT") (pintype "bidirectional"))
    )
    (net (code "50") (name "T_GND") (class "Default")
      (node (ref "JP9") (pin "1") (pinfunction "1_1") (pintype "passive"))
      (node (ref "R18") (pin "2") (pinfunction "2_2") (pintype "passive"))
      (node (ref "R19") (pin "2") (pinfunction "2_2") (pintype "passive"))
    )
    (net (code "51") (name "VIDEO_OUT") (class "Default")
      (node (ref "JP10") (pin "3") (pinfunction "3_3") (pintype "passive"))
      (node (ref "TP10") (pin "1") (pinfunction "1_1") (pintype "passive"))
      (node (ref "U4") (pin "4") (pinfunction "COM_4") (pintype "bidirectional"))
    )
    (net (code "52") (name "VUMB") (class "Default")
      (node (ref "D2") (pin "ANODE") (pinfunction "+_ANODE") (pintype "passive"))
      (node (ref "JP9") (pin "4") (pinfunction "4_4") (pintype "passive"))
      (node (ref "U1") (pin "VCC") (pinfunction "VCC_VCC") (pintype "bidirectional"))
    )
    (net (code "53") (name "unconnected-(JP1-Pad3)") (class "Default")
      (node (ref "JP1") (pin "3") (pinfunction "3_3") (pintype "passive"))
    )
    (net (code "54") (name "unconnected-(JP2-Pad3)") (class "Default")
      (node (ref "JP2") (pin "3") (pinfunction "3_3") (pintype "passive"))
    )
    (net (code "55") (name "unconnected-(JP3-Pad3)") (class "Default")
      (node (ref "JP3") (pin "3") (pinfunction "3_3") (pintype "passive"))
    )
    (net (code "56") (name "unconnected-(JP4-Pad3)") (class "Default")
      (node (ref "JP4") (pin "3") (pinfunction "3_3") (pintype "passive"))
    )
    (net (code "57") (name "unconnected-(JP5-Pad3)") (class "Default")
      (node (ref "JP5") (pin "3") (pinfunction "3_3") (pintype "passive"))
    )
    (net (code "58") (name "unconnected-(JP6-Pad3)") (class "Default")
      (node (ref "JP6") (pin "3") (pinfunction "3_3") (pintype "passive"))
    )
    (net (code "59") (name "unconnected-(JP7-Pad3)") (class "Default")
      (node (ref "JP7") (pin "3") (pinfunction "3_3") (pintype "passive"))
    )
    (net (code "60") (name "unconnected-(U5-TB-Pad7)") (class "Default")
      (node (ref "U5") (pin "7") (pinfunction "TB_7") (pintype "bidirectional"))
    )
    (net (code "61") (name "unconnected-(U5-{slash}2-Pad1)") (class "Default")
      (node (ref "U5") (pin "1") (pinfunction "/2_1") (pintype "bidirectional"))
    )
    (net (code "62") (name "~{TIMER_OUTPUT}") (class "Default")
      (node (ref "TP9") (pin "1") (pinfunction "1_1") (pintype "passive"))
      (node (ref "U4") (pin "6") (pinfunction "IN_6") (pintype "bidirectional"))
      (node (ref "U5") (pin "2") (pinfunction "/128_2") (pintype "bidirectional"))
      (node (ref "U5") (pin "4") (pinfunction "RESET_4") (pintype "bidirectional"))
    )
  )
)
